# usb_uart.net
KiCad netlist of a schematic drawn in Altium Designer
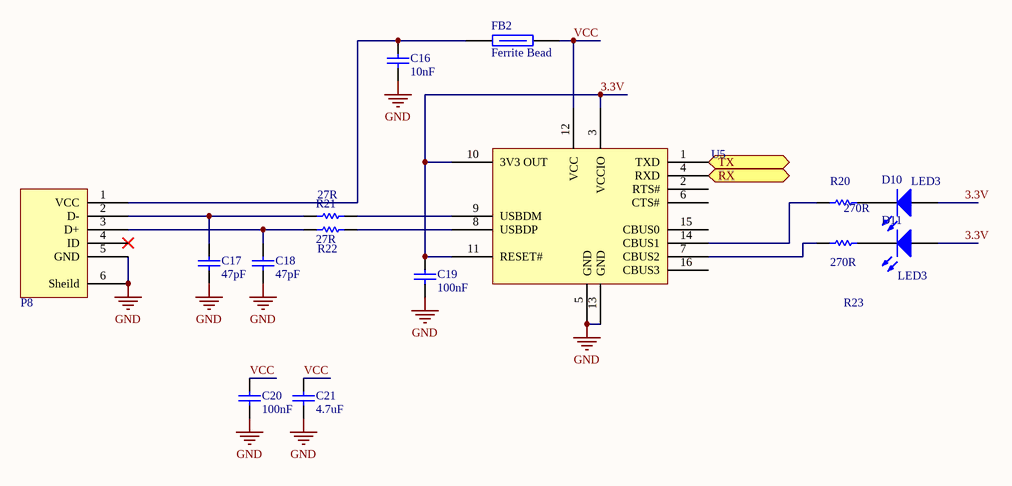
[diagram p0: usb_uart.SchDoc]

(export (version "E")
  (design (tool "Eeschema 10.0.6"))
  (components
    (comp (ref "C16")
      (value "10nF")
      (footprint "1608[0603]")
      (description "Capacitor")
      (fields (field (name "Comment") "Cap") (field (name "PUBLISHER") "Altium Limited"))
      (libsource (lib "Schematic Lib") (part "Cap"))
    )
    (comp (ref "C17")
      (value "47pF")
      (footprint "1608[0603]")
      (description "Capacitor")
      (fields (field (name "Comment") "Cap") (field (name "PUBLISHER") "Altium Limited"))
      (libsource (lib "Schematic Lib") (part "Cap"))
    )
    (comp (ref "C18")
      (value "47pF")
      (footprint "1608[0603]")
      (description "Capacitor")
      (fields (field (name "Comment") "Cap") (field (name "PUBLISHER") "Altium Limited"))
      (libsource (lib "Schematic Lib") (part "Cap"))
    )
    (comp (ref "C19")
      (value "100nF")
      (footprint "1608[0603]")
      (description "Capacitor")
      (fields (field (name "Comment") "Cap") (field (name "PUBLISHER") "Altium Limited"))
      (libsource (lib "Schematic Lib") (part "Cap"))
    )
    (comp (ref "C20")
      (value "100nF")
      (footprint "1608[0603]")
      (description "Capacitor")
      (fields (field (name "Comment") "Cap") (field (name "PUBLISHER") "Altium Limited"))
      (libsource (lib "Schematic Lib") (part "Cap"))
    )
    (comp (ref "C21")
      (value "4.7uF")
      (footprint "1608[0603]")
      (description "Capacitor")
      (fields (field (name "Comment") "Cap") (field (name "PUBLISHER") "Altium Limited"))
      (libsource (lib "Schematic Lib") (part "Cap"))
    )
    (comp (ref "D10")
      (value "LED3")
      (footprint "LED 0805")
      (description "Typical BLUE SiC LED")
      (fields (field (name "PUBLISHER") "Altium Limited"))
      (libsource (lib "Miscellaneous Devices") (part "LED3"))
    )
    (comp (ref "D11")
      (value "LED3")
      (footprint "LED 0805")
      (description "Typical BLUE SiC LED")
      (fields (field (name "PUBLISHER") "Altium Limited"))
      (libsource (lib "Miscellaneous Devices") (part "LED3"))
    )
    (comp (ref "FB2")
      (value "Ferrite Bead")
      (footprint "ELE3PRO_2012:0603")
      (libsource (lib "Schematic Lib") (part "Ferrite Bead"))
    )
    (comp (ref "P8")
      (value "USB Micro B")
      (footprint "USB micro B")
      (libsource (lib "Schlib1") (part "USB Micro B"))
    )
    (comp (ref "R20")
      (value "270R")
      (footprint "J1-0603")
      (description "Resistor 0805")
      (fields (field (name "Comment") "Res") (field (name "PUBLISHER") "Altium Limited"))
      (libsource (lib "Schematic Lib") (part "Res"))
    )
    (comp (ref "R21")
      (value "27R")
      (footprint "J1-0603")
      (description "Resistor 0805")
      (fields (field (name "Comment") "Res") (field (name "PUBLISHER") "Altium Limited"))
      (libsource (lib "Schematic Lib") (part "Res"))
    )
    (comp (ref "R22")
      (value "27R")
      (footprint "J1-0603")
      (description "Resistor 0805")
      (fields (field (name "Comment") "Res") (field (name "PUBLISHER") "Altium Limited"))
      (libsource (lib "Schematic Lib") (part "Res"))
    )
    (comp (ref "R23")
      (value "270R")
      (footprint "J1-0603")
      (description "Resistor 0805")
      (fields (field (name "Comment") "Res") (field (name "PUBLISHER") "Altium Limited"))
      (libsource (lib "Schematic Lib") (part "Res"))
    )
    (comp (ref "U5") (value "FT230XS") (footprint "SSOP16_N") (libsource (lib "Schlib1") (part "FT230XS")))
  )
  (nets
    (net (code "1") (name "/3.3V") (class "Default")
      (node (ref "C19") (pin "2") (pinfunction "2_2") (pintype "passive"))
      (node (ref "D10") (pin "1") (pinfunction "A_1") (pintype "passive"))
      (node (ref "D11") (pin "1") (pinfunction "A_1") (pintype "passive"))
      (node (ref "U5") (pin "10") (pinfunction "3V3_OUT_10") (pintype "passive"))
      (node (ref "U5") (pin "11") (pinfunction "RESET#_11") (pintype "passive"))
      (node (ref "U5") (pin "3") (pinfunction "VCCIO_3") (pintype "passive"))
    )
    (net (code "2") (name "/RX") (class "Default")
      (node (ref "U5") (pin "4") (pinfunction "RXD_4") (pintype "passive"))
    )
    (net (code "3") (name "/TX") (class "Default")
      (node (ref "U5") (pin "1") (pinfunction "TXD_1") (pintype "passive"))
    )
    (net (code "4") (name "/VCC") (class "Default")
      (node (ref "C20") (pin "2") (pinfunction "2_2") (pintype "passive"))
      (node (ref "C21") (pin "2") (pinfunction "2_2") (pintype "passive"))
      (node (ref "FB2") (pin "1") (pinfunction "1_1") (pintype "passive"))
      (node (ref "U5") (pin "12") (pinfunction "VCC_12") (pintype "passive"))
    )
    (net (code "5") (name "GND") (class "Default")
      (node (ref "C16") (pin "1") (pinfunction "1_1") (pintype "passive"))
      (node (ref "C17") (pin "1") (pinfunction "1_1") (pintype "passive"))
      (node (ref "C18") (pin "1") (pinfunction "1_1") (pintype "passive"))
      (node (ref "C19") (pin "1") (pinfunction "1_1") (pintype "passive"))
      (node (ref "C20") (pin "1") (pinfunction "1_1") (pintype "passive"))
      (node (ref "C21") (pin "1") (pinfunction "1_1") (pintype "passive"))
      (node (ref "P8") (pin "5") (pinfunction "GND_5") (pintype "passive"))
      (node (ref "P8") (pin "6") (pinfunction "Sheild_6") (pintype "passive"))
      (node (ref "U5") (pin "13") (pinfunction "GND_13") (pintype "passive"))
      (node (ref "U5") (pin "5") (pinfunction "GND_5") (pintype "passive"))
    )
    (net (code "6") (name "Net-(D10-K)") (class "Default")
      (node (ref "D10") (pin "2") (pinfunction "K_2") (pintype "passive"))
      (node (ref "R20") (pin "1") (pinfunction "1_1") (pintype "passive"))
    )
    (net (code "7") (name "Net-(D11-K)") (class "Default")
      (node (ref "D11") (pin "2") (pinfunction "K_2") (pintype "passive"))
      (node (ref "R23") (pin "1") (pinfunction "1_1") (pintype "passive"))
    )
    (net (code "8") (name "Net-(P8-D+)") (class "Default")
      (node (ref "C18") (pin "2") (pinfunction "2_2") (pintype "passive"))
      (node (ref "P8") (pin "3") (pinfunction "D+_3") (pintype "passive"))
      (node (ref "R22") (pin "2") (pinfunction "2_2") (pintype "passive"))
    )
    (net (code "9") (name "Net-(P8-D-)") (class "Default")
      (node (ref "C17") (pin "2") (pinfunction "2_2") (pintype "passive"))
      (node (ref "P8") (pin "2") (pinfunction "D-_2") (pintype "passive"))
      (node (ref "R21") (pin "2") (pinfunction "2_2") (pintype "passive"))
    )
    (net (code "10") (name "Net-(P8-VCC)") (class "Default")
      (node (ref "C16") (pin "2") (pinfunction "2_2") (pintype "passive"))
      (node (ref "FB2") (pin "2") (pinfunction "2_2") (pintype "passive"))
      (node (ref "P8") (pin "1") (pinfunction "VCC_1") (pintype "passive"))
    )
    (net (code "11") (name "Net-(U5-CBUS1)") (class "Default")
      (node (ref "R20") (pin "2") (pinfunction "2_2") (pintype "passive"))
      (node (ref "U5") (pin "14") (pinfunction "CBUS1_14") (pintype "passive"))
    )
    (net (code "12") (name "Net-(U5-CBUS2)") (class "Default")
      (node (ref "R23") (pin "2") (pinfunction "2_2") (pintype "passive"))
      (node (ref "U5") (pin "7") (pinfunction "CBUS2_7") (pintype "passive"))
    )
    (net (code "13") (name "Net-(U5-USBDM)") (class "Default")
      (node (ref "R21") (pin "1") (pinfunction "1_1") (pintype "passive"))
      (node (ref "U5") (pin "9") (pinfunction "USBDM_9") (pintype "passive"))
    )
    (net (code "14") (name "Net-(U5-USBDP)") (class "Default")
      (node (ref "R22") (pin "1") (pinfunction "1_1") (pintype "passive"))
      (node (ref "U5") (pin "8") (pinfunction "USBDP_8") (pintype "passive"))
    )
    (net (code "15") (name "unconnected-(P8-ID-Pad4)") (class "Default")
      (node (ref "P8") (pin "4") (pinfunction "ID_4") (pintype "passive+no_connect"))
    )
    (net (code "16") (name "unconnected-(U5-CBUS0-Pad15)") (class "Default")
      (node (ref "U5") (pin "15") (pinfunction "CBUS0_15") (pintype "passive"))
    )
    (net (code "17") (name "unconnected-(U5-CBUS3-Pad16)") (class "Default")
      (node (ref "U5") (pin "16") (pinfunction "CBUS3_16") (pintype "passive"))
    )
    (net (code "18") (name "unconnected-(U5-CTS#-Pad6)") (class "Default")
      (node (ref "U5") (pin "6") (pinfunction "CTS#_6") (pintype "passive"))
    )
    (net (code "19") (name "unconnected-(U5-RTS#-Pad2)") (class "Default")
      (node (ref "U5") (pin "2") (pinfunction "RTS#_2") (pintype "passive"))
    )
  )
)
